# emi_filter_ch0_b.net
KiCad netlist of a schematic drawn in Altium Designer
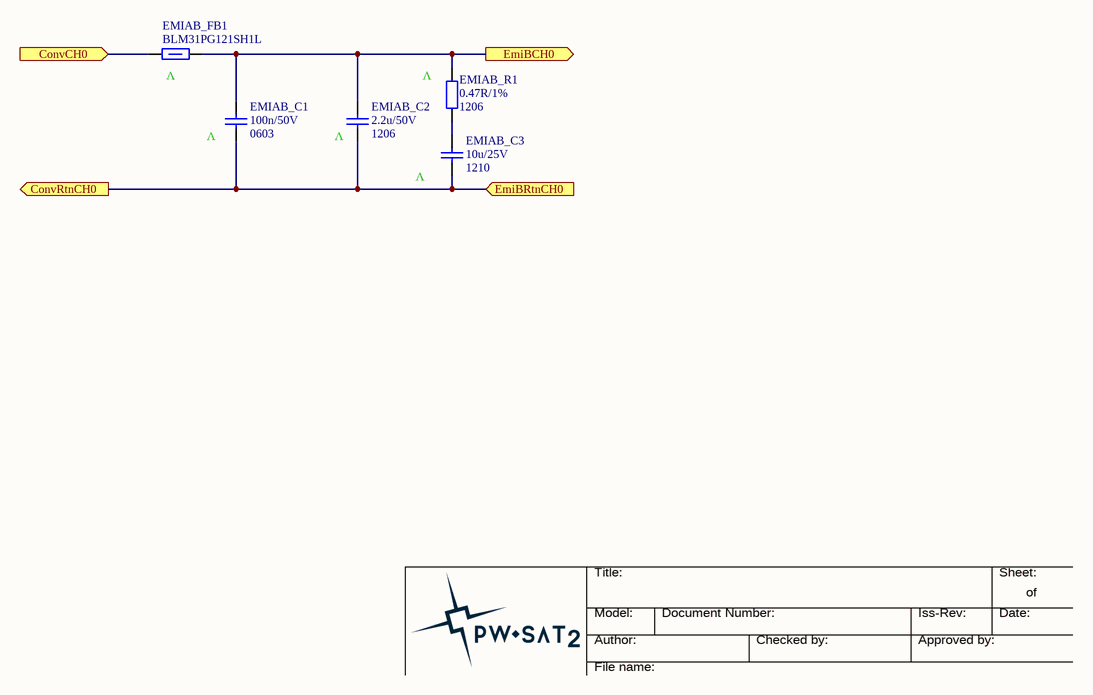
[diagram p0: emi_filter_ch0_b.SchDoc]

(export (version "E")
  (design (tool "Eeschema 10.0.6"))
  (components
    (comp (ref "EMIAB_C1")
      (value "100n/50V")
      (footprint "SMD_Capacitor_0603")
      (description "Ceramic Cap Kemet COTS 100n/50V X7R 0603")
      (fields
        (field (name "MANUFACTURER") "Kemet")
        (field (name "MANUFACTURERPARTNUMBER") "C0603T104K5RALTU")
        (field (name "PACKAGE") "0603")
      )
      (libsource (lib "capacitors") (part "Cer_C0603T104K5RALTU"))
    )
    (comp (ref "EMIAB_C2")
      (value "2.2u/50V")
      (footprint "SMD_Capacitor_1206")
      (description "Ceramic Cap Murata Automotive 2.2u/50V X7R 1206")
      (fields
        (field (name "MANUFACTURER") "Murata")
        (field (name "MANUFACTURERPARTNUMBER") "GCJ31CR71H225KA12L")
        (field (name "PACKAGE") "1206")
      )
      (libsource (lib "capacitors") (part "Cer_GCJ31CR71H225KA12L"))
    )
    (comp (ref "EMIAB_C3")
      (value "10u/25V")
      (footprint "SMD_Capacitor_1210")
      (description "Ceramic Cap Murata Automotive 10u/25V X7R 1210")
      (fields
        (field (name "MANUFACTURER") "Murata")
        (field (name "MANUFACTURERPARTNUMBER") "GCJ32ER71E106KA12L")
        (field (name "PACKAGE") "1210")
      )
      (libsource (lib "capacitors") (part "Cer_GCJ32ER71E106KA12L"))
    )
    (comp (ref "EMIAB_FB1")
      (value "120R/100MHz")
      (footprint "SMD_FerriteBead_1206")
      (description "Ferrite bead, 1206, 0.02HM, 3.5A.")
      (fields (field (name "MANUFACTURER") "Murata") (field (name "MANUFACTURERPARTNUMBER") "BLM31PG121SH1L"))
      (libsource (lib "inductors") (part "BLM31PG121SH1L"))
    )
    (comp (ref "EMIAB_R1")
      (value "0.47R/1%")
      (footprint "SMD_Resistor_1206")
      (description "Panasonic Resistor 0.47R 1% 1206 330mW")
      (fields
        (field (name "MANUFACTURERPARTNUMBER") "ERJ-8BQFR47V")
        (field (name "MANUFACTURER") "Panasonic")
        (field (name "PACKAGE") "1206")
      )
      (libsource (lib "resistors") (part "ERJ-8BQFR47V"))
    )
  )
  (nets
    (net (code "1") (name "/ConvCH0") (class "Default")
      (node (ref "EMIAB_FB1") (pin "2") (pinfunction "2_2") (pintype "passive"))
    )
    (net (code "2") (name "/ConvRtnCH0") (class "Default")
      (node (ref "EMIAB_C1") (pin "2") (pinfunction "2_2") (pintype "passive"))
      (node (ref "EMIAB_C2") (pin "2") (pinfunction "2_2") (pintype "passive"))
      (node (ref "EMIAB_C3") (pin "2") (pinfunction "2_2") (pintype "passive"))
    )
    (net (code "3") (name "/EmiBCH0") (class "Default")
      (node (ref "EMIAB_C1") (pin "1") (pinfunction "1_1") (pintype "passive"))
      (node (ref "EMIAB_C2") (pin "1") (pinfunction "1_1") (pintype "passive"))
      (node (ref "EMIAB_FB1") (pin "1") (pinfunction "1_1") (pintype "passive"))
      (node (ref "EMIAB_R1") (pin "2") (pinfunction "2_2") (pintype "passive"))
    )
    (net (code "4") (name "Net-(EMIAB_C3-Pad1)") (class "Default")
      (node (ref "EMIAB_C3") (pin "1") (pinfunction "1_1") (pintype "passive"))
      (node (ref "EMIAB_R1") (pin "1") (pinfunction "1_1") (pintype "passive"))
    )
  )
)
